# ESP8266.net
KiCad netlist of a schematic drawn in Altium Designer
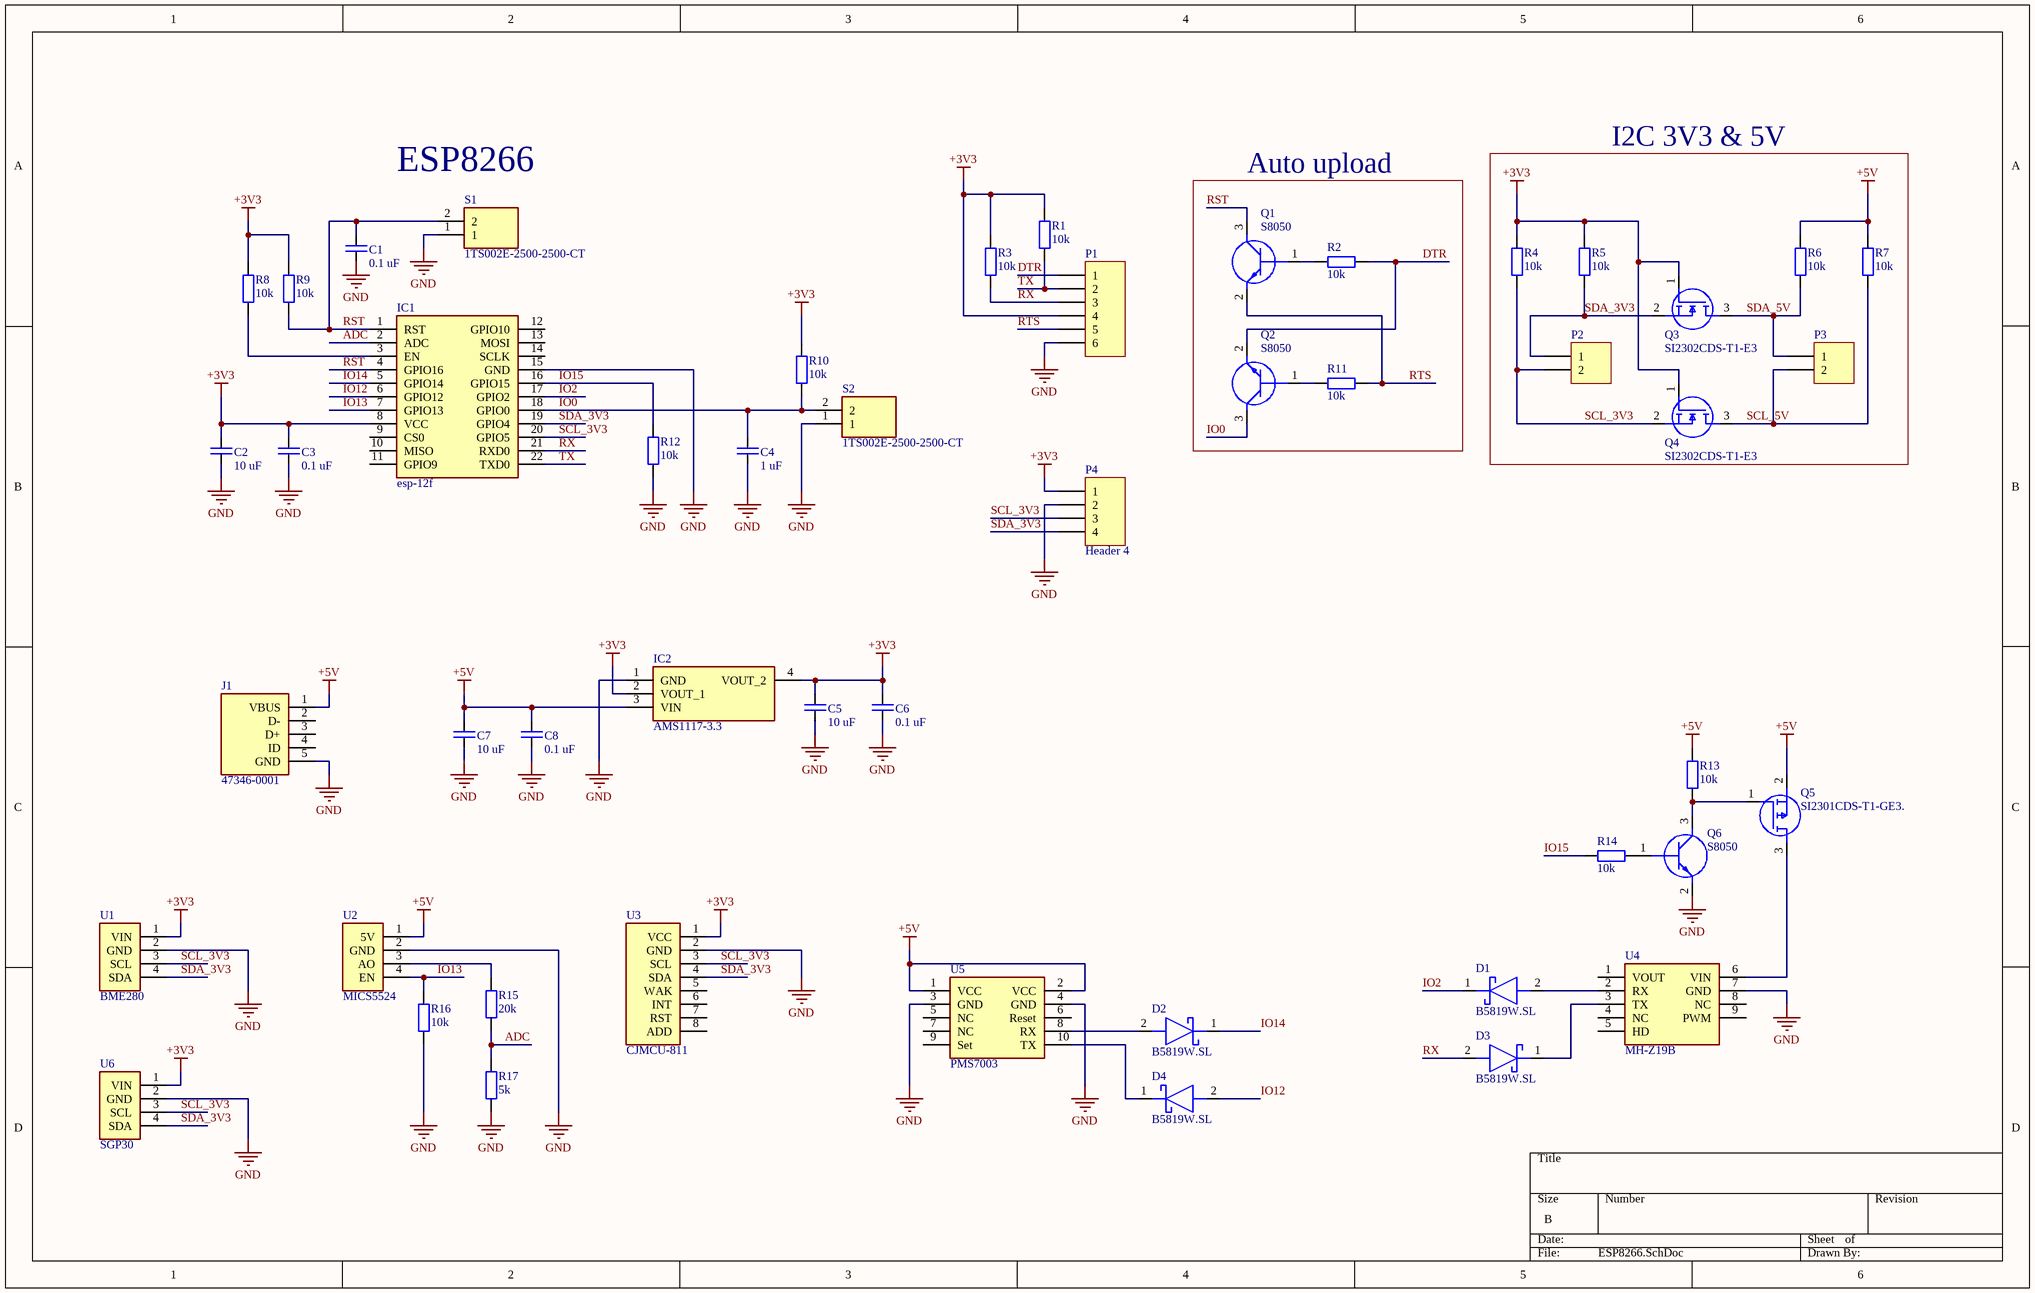
[diagram p0: ESP8266.SchDoc]

(export (version "E")
  (design (tool "Eeschema 10.0.6"))
  (components
    (comp (ref "C1")
      (value "0.1 uF")
      (footprint "C2012_0805I_N")
      (description "Capacitor")
      (libsource (lib "General") (part "C"))
    )
    (comp (ref "C2")
      (value "10 uF")
      (footprint "C2012_0805I_N")
      (description "Capacitor")
      (libsource (lib "General") (part "C"))
    )
    (comp (ref "C3")
      (value "0.1 uF")
      (footprint "C2012_0805I_N")
      (description "Capacitor")
      (libsource (lib "General") (part "C"))
    )
    (comp (ref "C4")
      (value "1 uF")
      (footprint "C2012_0805I_N")
      (description "Capacitor")
      (libsource (lib "General") (part "C"))
    )
    (comp (ref "C5")
      (value "10 uF")
      (footprint "C2012_0805I_N")
      (description "Capacitor")
      (libsource (lib "General") (part "C"))
    )
    (comp (ref "C6")
      (value "0.1 uF")
      (footprint "C2012_0805I_N")
      (description "Capacitor")
      (libsource (lib "General") (part "C"))
    )
    (comp (ref "C7")
      (value "10 uF")
      (footprint "C2012_0805I_N")
      (description "Capacitor")
      (libsource (lib "General") (part "C"))
    )
    (comp (ref "C8")
      (value "0.1 uF")
      (footprint "C2012_0805I_N")
      (description "Capacitor")
      (libsource (lib "General") (part "C"))
    )
    (comp (ref "D1")
      (value "B5819W.SL")
      (footprint "SamacSys:B5819WSL")
      (description "Schottky Diode")
      (libsource (lib "*") (part "B5819W.SL"))
    )
    (comp (ref "D2")
      (value "B5819W.SL")
      (footprint "SamacSys:B5819WSL")
      (description "Schottky Diode")
      (libsource (lib "*") (part "B5819W.SL"))
    )
    (comp (ref "D3")
      (value "B5819W.SL")
      (footprint "SamacSys:B5819WSL")
      (description "Schottky Diode")
      (libsource (lib "*") (part "B5819W.SL"))
    )
    (comp (ref "D4")
      (value "B5819W.SL")
      (footprint "SamacSys:B5819WSL")
      (description "Schottky Diode")
      (libsource (lib "*") (part "B5819W.SL"))
    )
    (comp (ref "IC1")
      (value "esp-12f")
      (footprint "SamacSys:esp12f")
      (description "Integrated Circuit")
      (libsource (lib "*") (part "esp-12f"))
    )
    (comp (ref "IC2")
      (value "AMS1117-3.3")
      (footprint "SamacSys:SOT229P700X180-4N")
      (description "Integrated Circuit")
      (libsource (lib "*") (part "AMS1117-3.3"))
    )
    (comp (ref "J1")
      (value "47346-0001")
      (footprint "SamacSys:47346-0001")
      (description "Connector")
      (fields (field (name "MOUSER PART NUMBER") "538-47346-0001"))
      (libsource (lib "*") (part "47346-0001"))
    )
    (comp (ref "P1")
      (value "~")
      (footprint "HDR1X6")
      (description "Header, 6-Pin")
      (fields (field (name "PUBLISHER") "Altium Limited"))
      (libsource (lib "Miscellaneous Connectors") (part "Header 6"))
    )
    (comp (ref "P2")
      (value "~")
      (footprint "HDR1X2")
      (description "Header, 2-Pin")
      (fields (field (name "PUBLISHER") "Altium Limited"))
      (libsource (lib "Miscellaneous Connectors") (part "Header 2"))
    )
    (comp (ref "P3")
      (value "~")
      (footprint "HDR1X2")
      (description "Header, 2-Pin")
      (fields (field (name "PUBLISHER") "Altium Limited"))
      (libsource (lib "Miscellaneous Connectors") (part "Header 2"))
    )
    (comp (ref "P4")
      (value "Header 4")
      (footprint "HDR1X4")
      (description "Header, 4-Pin")
      (fields (field (name "PUBLISHER") "Altium Limited"))
      (libsource (lib "Miscellaneous Connectors") (part "Header 4"))
    )
    (comp (ref "Q1")
      (value "S8050")
      (footprint "SamacSys:SOT95P240X110-3N")
      (description "Transistor BJT NPN")
      (fields (field (name "MANUFACTURER_PART_NUMBER") "S8050G"))
      (libsource (lib "SamacSys") (part "S8050"))
    )
    (comp (ref "Q2")
      (value "S8050")
      (footprint "SamacSys:SOT95P240X110-3N")
      (description "Transistor BJT NPN")
      (fields (field (name "MANUFACTURER_PART_NUMBER") "S8050G"))
      (libsource (lib "SamacSys") (part "S8050"))
    )
    (comp (ref "Q3")
      (value "SI2302CDS-T1-E3")
      (footprint "SamacSys:SOT95P237X112-3N")
      (description "MOSFET (N-Channel)")
      (fields (field (name "MOUSER PART NUMBER") "781-SI2302CDS-E3"))
      (libsource (lib "SamacSys") (part "SI2302CDS-T1-E3"))
    )
    (comp (ref "Q4")
      (value "SI2302CDS-T1-E3")
      (footprint "SamacSys:SOT95P237X112-3N")
      (description "MOSFET (N-Channel)")
      (fields (field (name "MOUSER PART NUMBER") "781-SI2302CDS-E3"))
      (libsource (lib "SamacSys") (part "SI2302CDS-T1-E3"))
    )
    (comp (ref "Q5")
      (value "SI2301CDS-T1-GE3.")
      (footprint "SamacSys:SOT95P237X112-3N")
      (description "MOSFET (P-Channel)")
      (libsource (lib "SamacSys") (part "SI2301CDS-T1-GE3."))
    )
    (comp (ref "Q6")
      (value "S8050")
      (footprint "SamacSys:SOT95P240X110-3N")
      (description "Transistor BJT NPN")
      (fields (field (name "MANUFACTURER_PART_NUMBER") "S8050G"))
      (libsource (lib "SamacSys") (part "S8050"))
    )
    (comp (ref "R1")
      (value "10k")
      (footprint "R2012_0805I_N")
      (description "R")
      (libsource (lib "General") (part "R"))
    )
    (comp (ref "R2")
      (value "10k")
      (footprint "R2012_0805I_N")
      (description "R")
      (libsource (lib "General") (part "R"))
    )
    (comp (ref "R3")
      (value "10k")
      (footprint "R2012_0805I_N")
      (description "R")
      (libsource (lib "General") (part "R"))
    )
    (comp (ref "R4")
      (value "10k")
      (footprint "R2012_0805I_N")
      (description "R")
      (libsource (lib "General") (part "R"))
    )
    (comp (ref "R5")
      (value "10k")
      (footprint "R2012_0805I_N")
      (description "R")
      (libsource (lib "General") (part "R"))
    )
    (comp (ref "R6")
      (value "10k")
      (footprint "R2012_0805I_N")
      (description "R")
      (libsource (lib "General") (part "R"))
    )
    (comp (ref "R7")
      (value "10k")
      (footprint "R2012_0805I_N")
      (description "R")
      (libsource (lib "General") (part "R"))
    )
    (comp (ref "R8")
      (value "10k")
      (footprint "R2012_0805I_N")
      (description "R")
      (libsource (lib "General") (part "R"))
    )
    (comp (ref "R9")
      (value "10k")
      (footprint "R2012_0805I_N")
      (description "R")
      (libsource (lib "General") (part "R"))
    )
    (comp (ref "R10")
      (value "10k")
      (footprint "R2012_0805I_N")
      (description "R")
      (libsource (lib "General") (part "R"))
    )
    (comp (ref "R11")
      (value "10k")
      (footprint "R2012_0805I_N")
      (description "R")
      (libsource (lib "General") (part "R"))
    )
    (comp (ref "R12")
      (value "10k")
      (footprint "R2012_0805I_N")
      (description "R")
      (libsource (lib "General") (part "R"))
    )
    (comp (ref "R13")
      (value "10k")
      (footprint "R2012_0805I_N")
      (description "R")
      (libsource (lib "General") (part "R"))
    )
    (comp (ref "R14")
      (value "10k")
      (footprint "R2012_0805I_N")
      (description "R")
      (libsource (lib "General") (part "R"))
    )
    (comp (ref "R15")
      (value "20k")
      (footprint "R2012_0805I_N")
      (description "R")
      (libsource (lib "General") (part "R"))
    )
    (comp (ref "R16")
      (value "10k")
      (footprint "R2012_0805I_N")
      (description "R")
      (libsource (lib "General") (part "R"))
    )
    (comp (ref "R17")
      (value "5k")
      (footprint "R2012_0805I_N")
      (description "R")
      (libsource (lib "General") (part "R"))
    )
    (comp (ref "S1")
      (value "1TS002E-2500-2500-CT")
      (footprint "1TS002E25002500CT")
      (description "Switch")
      (libsource (lib "SamacSys") (part "1TS002E-2500-2500-CT"))
    )
    (comp (ref "S2")
      (value "1TS002E-2500-2500-CT")
      (footprint "1TS002E25002500CT")
      (description "Switch")
      (libsource (lib "SamacSys") (part "1TS002E-2500-2500-CT"))
    )
    (comp (ref "U1") (value "BME280") (footprint "BME280") (libsource (lib "SamacSys") (part "BME280")))
    (comp (ref "U2") (value "MICS5524") (footprint "MICS5524") (libsource (lib "SamacSys") (part "MICS5524")))
    (comp (ref "U3")
      (value "CJMCU-811")
      (footprint "CJMCU-811")
      (libsource (lib "SamacSys") (part "CJMCU-811"))
    )
    (comp (ref "U4") (value "MH-Z19B") (footprint "MH-Z19B") (libsource (lib "SamacSys") (part "MH-Z19B")))
    (comp (ref "U5") (value "PMS7003") (footprint "PMS7003") (libsource (lib "SamacSys") (part "PMS7003")))
    (comp (ref "U6") (value "SGP30") (footprint "SGP30") (libsource (lib "SamacSys") (part "SGP30")))
  )
  (nets
    (net (code "1") (name "+3V3") (class "Default")
      (node (ref "C2") (pin "1") (pinfunction "1_1") (pintype "passive"))
      (node (ref "C3") (pin "1") (pinfunction "1_1") (pintype "passive"))
      (node (ref "C5") (pin "1") (pinfunction "1_1") (pintype "passive"))
      (node (ref "C6") (pin "1") (pinfunction "1_1") (pintype "passive"))
      (node (ref "IC1") (pin "8") (pinfunction "VCC_8") (pintype "passive"))
      (node (ref "IC2") (pin "2") (pinfunction "VOUT_1_2") (pintype "passive"))
      (node (ref "IC2") (pin "4") (pinfunction "VOUT_2_4") (pintype "passive"))
      (node (ref "P1") (pin "4") (pinfunction "4_4") (pintype "passive"))
      (node (ref "P4") (pin "1") (pinfunction "1_1") (pintype "passive"))
      (node (ref "Q3") (pin "1") (pinfunction "G_1") (pintype "passive"))
      (node (ref "Q4") (pin "1") (pinfunction "G_1") (pintype "passive"))
      (node (ref "R1") (pin "2") (pintype "passive"))
      (node (ref "R10") (pin "2") (pintype "passive"))
      (node (ref "R3") (pin "2") (pintype "passive"))
      (node (ref "R4") (pin "2") (pintype "passive"))
      (node (ref "R5") (pin "2") (pintype "passive"))
      (node (ref "R8") (pin "2") (pintype "passive"))
      (node (ref "R9") (pin "2") (pintype "passive"))
      (node (ref "U1") (pin "1") (pinfunction "VIN_1") (pintype "passive"))
      (node (ref "U3") (pin "1") (pinfunction "VCC_1") (pintype "passive"))
      (node (ref "U6") (pin "1") (pinfunction "VIN_1") (pintype "passive"))
    )
    (net (code "2") (name "+5V") (class "Default")
      (node (ref "C7") (pin "1") (pinfunction "1_1") (pintype "passive"))
      (node (ref "C8") (pin "1") (pinfunction "1_1") (pintype "passive"))
      (node (ref "IC2") (pin "3") (pinfunction "VIN_3") (pintype "passive"))
      (node (ref "J1") (pin "1") (pinfunction "VBUS_1") (pintype "passive"))
      (node (ref "Q5") (pin "2") (pinfunction "S_2") (pintype "passive"))
      (node (ref "R13") (pin "2") (pintype "passive"))
      (node (ref "R6") (pin "2") (pintype "passive"))
      (node (ref "R7") (pin "2") (pintype "passive"))
      (node (ref "U2") (pin "1") (pinfunction "5V_1") (pintype "passive"))
      (node (ref "U5") (pin "1") (pinfunction "VCC_1") (pintype "passive"))
      (node (ref "U5") (pin "2") (pinfunction "VCC_2") (pintype "passive"))
    )
    (net (code "3") (name "/ADC") (class "Default")
      (node (ref "IC1") (pin "2") (pinfunction "ADC_2") (pintype "passive"))
      (node (ref "R15") (pin "1") (pintype "passive"))
      (node (ref "R17") (pin "2") (pintype "passive"))
    )
    (net (code "4") (name "/DTR") (class "Default")
      (node (ref "P1") (pin "1") (pinfunction "1_1") (pintype "passive"))
      (node (ref "Q2") (pin "2") (pinfunction "E_2") (pintype "passive"))
      (node (ref "R2") (pin "1") (pintype "passive"))
    )
    (net (code "5") (name "/IO0") (class "Default")
      (node (ref "C4") (pin "1") (pinfunction "1_1") (pintype "passive"))
      (node (ref "IC1") (pin "18") (pinfunction "GPIO0_18") (pintype "passive"))
      (node (ref "Q2") (pin "3") (pinfunction "C_3") (pintype "passive"))
      (node (ref "R10") (pin "1") (pintype "passive"))
      (node (ref "S2") (pin "2") (pinfunction "2_2") (pintype "passive"))
    )
    (net (code "6") (name "/IO2") (class "Default")
      (node (ref "D1") (pin "1") (pinfunction "K_1") (pintype "passive"))
      (node (ref "IC1") (pin "17") (pinfunction "GPIO2_17") (pintype "passive"))
    )
    (net (code "7") (name "/IO12") (class "Default")
      (node (ref "D4") (pin "2") (pinfunction "A_2") (pintype "passive"))
      (node (ref "IC1") (pin "6") (pinfunction "GPIO12_6") (pintype "passive"))
    )
    (net (code "8") (name "/IO13") (class "Default")
      (node (ref "IC1") (pin "7") (pinfunction "GPIO13_7") (pintype "passive"))
      (node (ref "R16") (pin "2") (pintype "passive"))
      (node (ref "U2") (pin "4") (pinfunction "EN_4") (pintype "passive"))
    )
    (net (code "9") (name "/IO14") (class "Default")
      (node (ref "D2") (pin "1") (pinfunction "K_1") (pintype "passive"))
      (node (ref "IC1") (pin "5") (pinfunction "GPIO14_5") (pintype "passive"))
    )
    (net (code "10") (name "/IO15") (class "Default")
      (node (ref "IC1") (pin "16") (pinfunction "GPIO15_16") (pintype "passive"))
      (node (ref "R12") (pin "2") (pintype "passive"))
      (node (ref "R14") (pin "2") (pintype "passive"))
    )
    (net (code "11") (name "/RST") (class "Default")
      (node (ref "C1") (pin "1") (pinfunction "1_1") (pintype "passive"))
      (node (ref "IC1") (pin "1") (pinfunction "RST_1") (pintype "passive"))
      (node (ref "IC1") (pin "4") (pinfunction "GPIO16_4") (pintype "passive"))
      (node (ref "Q1") (pin "3") (pinfunction "C_3") (pintype "passive"))
      (node (ref "R9") (pin "1") (pintype "passive"))
      (node (ref "S1") (pin "2") (pinfunction "2_2") (pintype "passive"))
    )
    (net (code "12") (name "/RTS") (class "Default")
      (node (ref "P1") (pin "5") (pinfunction "5_5") (pintype "passive"))
      (node (ref "Q1") (pin "2") (pinfunction "E_2") (pintype "passive"))
      (node (ref "R11") (pin "1") (pintype "passive"))
    )
    (net (code "13") (name "/RX") (class "Default")
      (node (ref "D3") (pin "2") (pinfunction "A_2") (pintype "passive"))
      (node (ref "IC1") (pin "21") (pinfunction "RXD0_21") (pintype "passive"))
      (node (ref "P1") (pin "3") (pinfunction "3_3") (pintype "passive"))
      (node (ref "R3") (pin "1") (pintype "passive"))
    )
    (net (code "14") (name "/SCL_3V3") (class "Default")
      (node (ref "IC1") (pin "20") (pinfunction "GPIO5_20") (pintype "passive"))
      (node (ref "P2") (pin "2") (pinfunction "2_2") (pintype "passive"))
      (node (ref "P4") (pin "3") (pinfunction "3_3") (pintype "passive"))
      (node (ref "Q4") (pin "2") (pinfunction "S_2") (pintype "passive"))
      (node (ref "R4") (pin "1") (pintype "passive"))
      (node (ref "U1") (pin "3") (pinfunction "SCL_3") (pintype "passive"))
      (node (ref "U3") (pin "3") (pinfunction "SCL_3") (pintype "passive"))
      (node (ref "U6") (pin "3") (pinfunction "SCL_3") (pintype "passive"))
    )
    (net (code "15") (name "/SCL_5V") (class "Default")
      (node (ref "P3") (pin "2") (pinfunction "2_2") (pintype "passive"))
      (node (ref "Q4") (pin "3") (pinfunction "D_3") (pintype "passive"))
      (node (ref "R7") (pin "1") (pintype "passive"))
    )
    (net (code "16") (name "/SDA_3V3") (class "Default")
      (node (ref "IC1") (pin "19") (pinfunction "GPIO4_19") (pintype "passive"))
      (node (ref "P2") (pin "1") (pinfunction "1_1") (pintype "passive"))
      (node (ref "P4") (pin "4") (pinfunction "4_4") (pintype "passive"))
      (node (ref "Q3") (pin "2") (pinfunction "S_2") (pintype "passive"))
      (node (ref "R5") (pin "1") (pintype "passive"))
      (node (ref "U1") (pin "4") (pinfunction "SDA_4") (pintype "passive"))
      (node (ref "U3") (pin "4") (pinfunction "SDA_4") (pintype "passive"))
      (node (ref "U6") (pin "4") (pinfunction "SDA_4") (pintype "passive"))
    )
    (net (code "17") (name "/SDA_5V") (class "Default")
      (node (ref "P3") (pin "1") (pinfunction "1_1") (pintype "passive"))
      (node (ref "Q3") (pin "3") (pinfunction "D_3") (pintype "passive"))
      (node (ref "R6") (pin "1") (pintype "passive"))
    )
    (net (code "18") (name "/TX") (class "Default")
      (node (ref "IC1") (pin "22") (pinfunction "TXD0_22") (pintype "passive"))
      (node (ref "P1") (pin "2") (pinfunction "2_2") (pintype "passive"))
      (node (ref "R1") (pin "1") (pintype "passive"))
    )
    (net (code "19") (name "GND") (class "Default")
      (node (ref "C1") (pin "2") (pinfunction "2_2") (pintype "passive"))
      (node (ref "C2") (pin "2") (pinfunction "2_2") (pintype "passive"))
      (node (ref "C3") (pin "2") (pinfunction "2_2") (pintype "passive"))
      (node (ref "C4") (pin "2") (pinfunction "2_2") (pintype "passive"))
      (node (ref "C5") (pin "2") (pinfunction "2_2") (pintype "passive"))
      (node (ref "C6") (pin "2") (pinfunction "2_2") (pintype "passive"))
      (node (ref "C7") (pin "2") (pinfunction "2_2") (pintype "passive"))
      (node (ref "C8") (pin "2") (pinfunction "2_2") (pintype "passive"))
      (node (ref "IC1") (pin "15") (pinfunction "GND_15") (pintype "passive"))
      (node (ref "IC2") (pin "1") (pinfunction "GND_1") (pintype "passive"))
      (node (ref "J1") (pin "5") (pinfunction "GND_5") (pintype "passive"))
      (node (ref "P1") (pin "6") (pinfunction "6_6") (pintype "passive"))
      (node (ref "P4") (pin "2") (pinfunction "2_2") (pintype "passive"))
      (node (ref "Q6") (pin "2") (pinfunction "E_2") (pintype "passive"))
      (node (ref "R12") (pin "1") (pintype "passive"))
      (node (ref "R16") (pin "1") (pintype "passive"))
      (node (ref "R17") (pin "1") (pintype "passive"))
      (node (ref "S1") (pin "1") (pinfunction "1_1") (pintype "passive"))
      (node (ref "S2") (pin "1") (pinfunction "1_1") (pintype "passive"))
      (node (ref "U1") (pin "2") (pinfunction "GND_2") (pintype "passive"))
      (node (ref "U2") (pin "2") (pinfunction "GND_2") (pintype "passive"))
      (node (ref "U3") (pin "2") (pinfunction "GND_2") (pintype "passive"))
      (node (ref "U4") (pin "7") (pinfunction "GND_7") (pintype "passive"))
      (node (ref "U5") (pin "3") (pinfunction "GND_3") (pintype "passive"))
      (node (ref "U5") (pin "4") (pinfunction "GND_4") (pintype "passive"))
      (node (ref "U6") (pin "2") (pinfunction "GND_2") (pintype "passive"))
    )
    (net (code "20") (name "Net-(D1-A)") (class "Default")
      (node (ref "D1") (pin "2") (pinfunction "A_2") (pintype "passive"))
      (node (ref "U4") (pin "2") (pinfunction "RX_2") (pintype "passive"))
    )
    (net (code "21") (name "Net-(D2-A)") (class "Default")
      (node (ref "D2") (pin "2") (pinfunction "A_2") (pintype "passive"))
      (node (ref "U5") (pin "8") (pinfunction "RX_8") (pintype "passive"))
    )
    (net (code "22") (name "Net-(D3-K)") (class "Default")
      (node (ref "D3") (pin "1") (pinfunction "K_1") (pintype "passive"))
      (node (ref "U4") (pin "3") (pinfunction "TX_3") (pintype "passive"))
    )
    (net (code "23") (name "Net-(D4-K)") (class "Default")
      (node (ref "D4") (pin "1") (pinfunction "K_1") (pintype "passive"))
      (node (ref "U5") (pin "10") (pinfunction "TX_10") (pintype "passive"))
    )
    (net (code "24") (name "Net-(IC1-EN)") (class "Default")
      (node (ref "IC1") (pin "3") (pinfunction "EN_3") (pintype "passive"))
      (node (ref "R8") (pin "1") (pintype "passive"))
    )
    (net (code "25") (name "Net-(Q1-B)") (class "Default")
      (node (ref "Q1") (pin "1") (pinfunction "B_1") (pintype "passive"))
      (node (ref "R2") (pin "2") (pintype "passive"))
    )
    (net (code "26") (name "Net-(Q2-B)") (class "Default")
      (node (ref "Q2") (pin "1") (pinfunction "B_1") (pintype "passive"))
      (node (ref "R11") (pin "2") (pintype "passive"))
    )
    (net (code "27") (name "Net-(Q5-D)") (class "Default")
      (node (ref "Q5") (pin "3") (pinfunction "D_3") (pintype "passive"))
      (node (ref "U4") (pin "6") (pinfunction "VIN_6") (pintype "passive"))
    )
    (net (code "28") (name "Net-(Q5-G)") (class "Default")
      (node (ref "Q5") (pin "1") (pinfunction "G_1") (pintype "passive"))
      (node (ref "Q6") (pin "3") (pinfunction "C_3") (pintype "passive"))
      (node (ref "R13") (pin "1") (pintype "passive"))
    )
    (net (code "29") (name "Net-(Q6-B)") (class "Default")
      (node (ref "Q6") (pin "1") (pinfunction "B_1") (pintype "passive"))
      (node (ref "R14") (pin "1") (pintype "passive"))
    )
    (net (code "30") (name "Net-(U2-AO)") (class "Default")
      (node (ref "R15") (pin "2") (pintype "passive"))
      (node (ref "U2") (pin "3") (pinfunction "AO_3") (pintype "passive"))
    )
    (net (code "31") (name "unconnected-(IC1-CS0-Pad9)") (class "Default")
      (node (ref "IC1") (pin "9") (pinfunction "CS0_9") (pintype "passive"))
    )
    (net (code "32") (name "unconnected-(IC1-GPIO9-Pad11)") (class "Default")
      (node (ref "IC1") (pin "11") (pinfunction "GPIO9_11") (pintype "passive"))
    )
    (net (code "33") (name "unconnected-(IC1-GPIO10-Pad12)") (class "Default")
      (node (ref "IC1") (pin "12") (pinfunction "GPIO10_12") (pintype "passive"))
    )
    (net (code "34") (name "unconnected-(IC1-MISO-Pad10)") (class "Default")
      (node (ref "IC1") (pin "10") (pinfunction "MISO_10") (pintype "passive"))
    )
    (net (code "35") (name "unconnected-(IC1-MOSI-Pad13)") (class "Default")
      (node (ref "IC1") (pin "13") (pinfunction "MOSI_13") (pintype "passive"))
    )
    (net (code "36") (name "unconnected-(IC1-SCLK-Pad14)") (class "Default")
      (node (ref "IC1") (pin "14") (pinfunction "SCLK_14") (pintype "passive"))
    )
    (net (code "37") (name "unconnected-(J1-D+-Pad3)") (class "Default")
      (node (ref "J1") (pin "3") (pinfunction "D+_3") (pintype "passive"))
    )
    (net (code "38") (name "unconnected-(J1-D--Pad2)") (class "Default")
      (node (ref "J1") (pin "2") (pinfunction "D-_2") (pintype "passive"))
    )
    (net (code "39") (name "unconnected-(J1-ID-Pad4)") (class "Default")
      (node (ref "J1") (pin "4") (pinfunction "ID_4") (pintype "passive"))
    )
    (net (code "40") (name "unconnected-(U3-ADD-Pad8)") (class "Default")
      (node (ref "U3") (pin "8") (pinfunction "ADD_8") (pintype "passive"))
    )
    (net (code "41") (name "unconnected-(U3-INT-Pad6)") (class "Default")
      (node (ref "U3") (pin "6") (pinfunction "INT_6") (pintype "passive"))
    )
    (net (code "42") (name "unconnected-(U3-RST-Pad7)") (class "Default")
      (node (ref "U3") (pin "7") (pinfunction "RST_7") (pintype "passive"))
    )
    (net (code "43") (name "unconnected-(U3-WAK-Pad5)") (class "Default")
      (node (ref "U3") (pin "5") (pinfunction "WAK_5") (pintype "passive"))
    )
    (net (code "44") (name "unconnected-(U4-HD-Pad5)") (class "Default")
      (node (ref "U4") (pin "5") (pinfunction "HD_5") (pintype "passive"))
    )
    (net (code "45") (name "unconnected-(U4-NC-Pad4)") (class "Default")
      (node (ref "U4") (pin "4") (pinfunction "NC_4") (pintype "passive"))
    )
    (net (code "46") (name "unconnected-(U4-NC-Pad8)") (class "Default")
      (node (ref "U4") (pin "8") (pinfunction "NC_8") (pintype "passive"))
    )
    (net (code "47") (name "unconnected-(U4-PWM-Pad9)") (class "Default")
      (node (ref "U4") (pin "9") (pinfunction "PWM_9") (pintype "passive"))
    )
    (net (code "48") (name "unconnected-(U4-VOUT-Pad1)") (class "Default")
      (node (ref "U4") (pin "1") (pinfunction "VOUT_1") (pintype "passive"))
    )
    (net (code "49") (name "unconnected-(U5-NC-Pad5)") (class "Default")
      (node (ref "U5") (pin "5") (pinfunction "NC_5") (pintype "passive"))
    )
    (net (code "50") (name "unconnected-(U5-NC-Pad7)") (class "Default")
      (node (ref "U5") (pin "7") (pinfunction "NC_7") (pintype "passive"))
    )
    (net (code "51") (name "unconnected-(U5-Reset-Pad6)") (class "Default")
      (node (ref "U5") (pin "6") (pinfunction "Reset_6") (pintype "passive"))
    )
    (net (code "52") (name "unconnected-(U5-Set-Pad9)") (class "Default")
      (node (ref "U5") (pin "9") (pinfunction "Set_9") (pintype "passive"))
    )
  )
)
